# mouseproxy.net
KiCad netlist of a schematic drawn in EAGLE
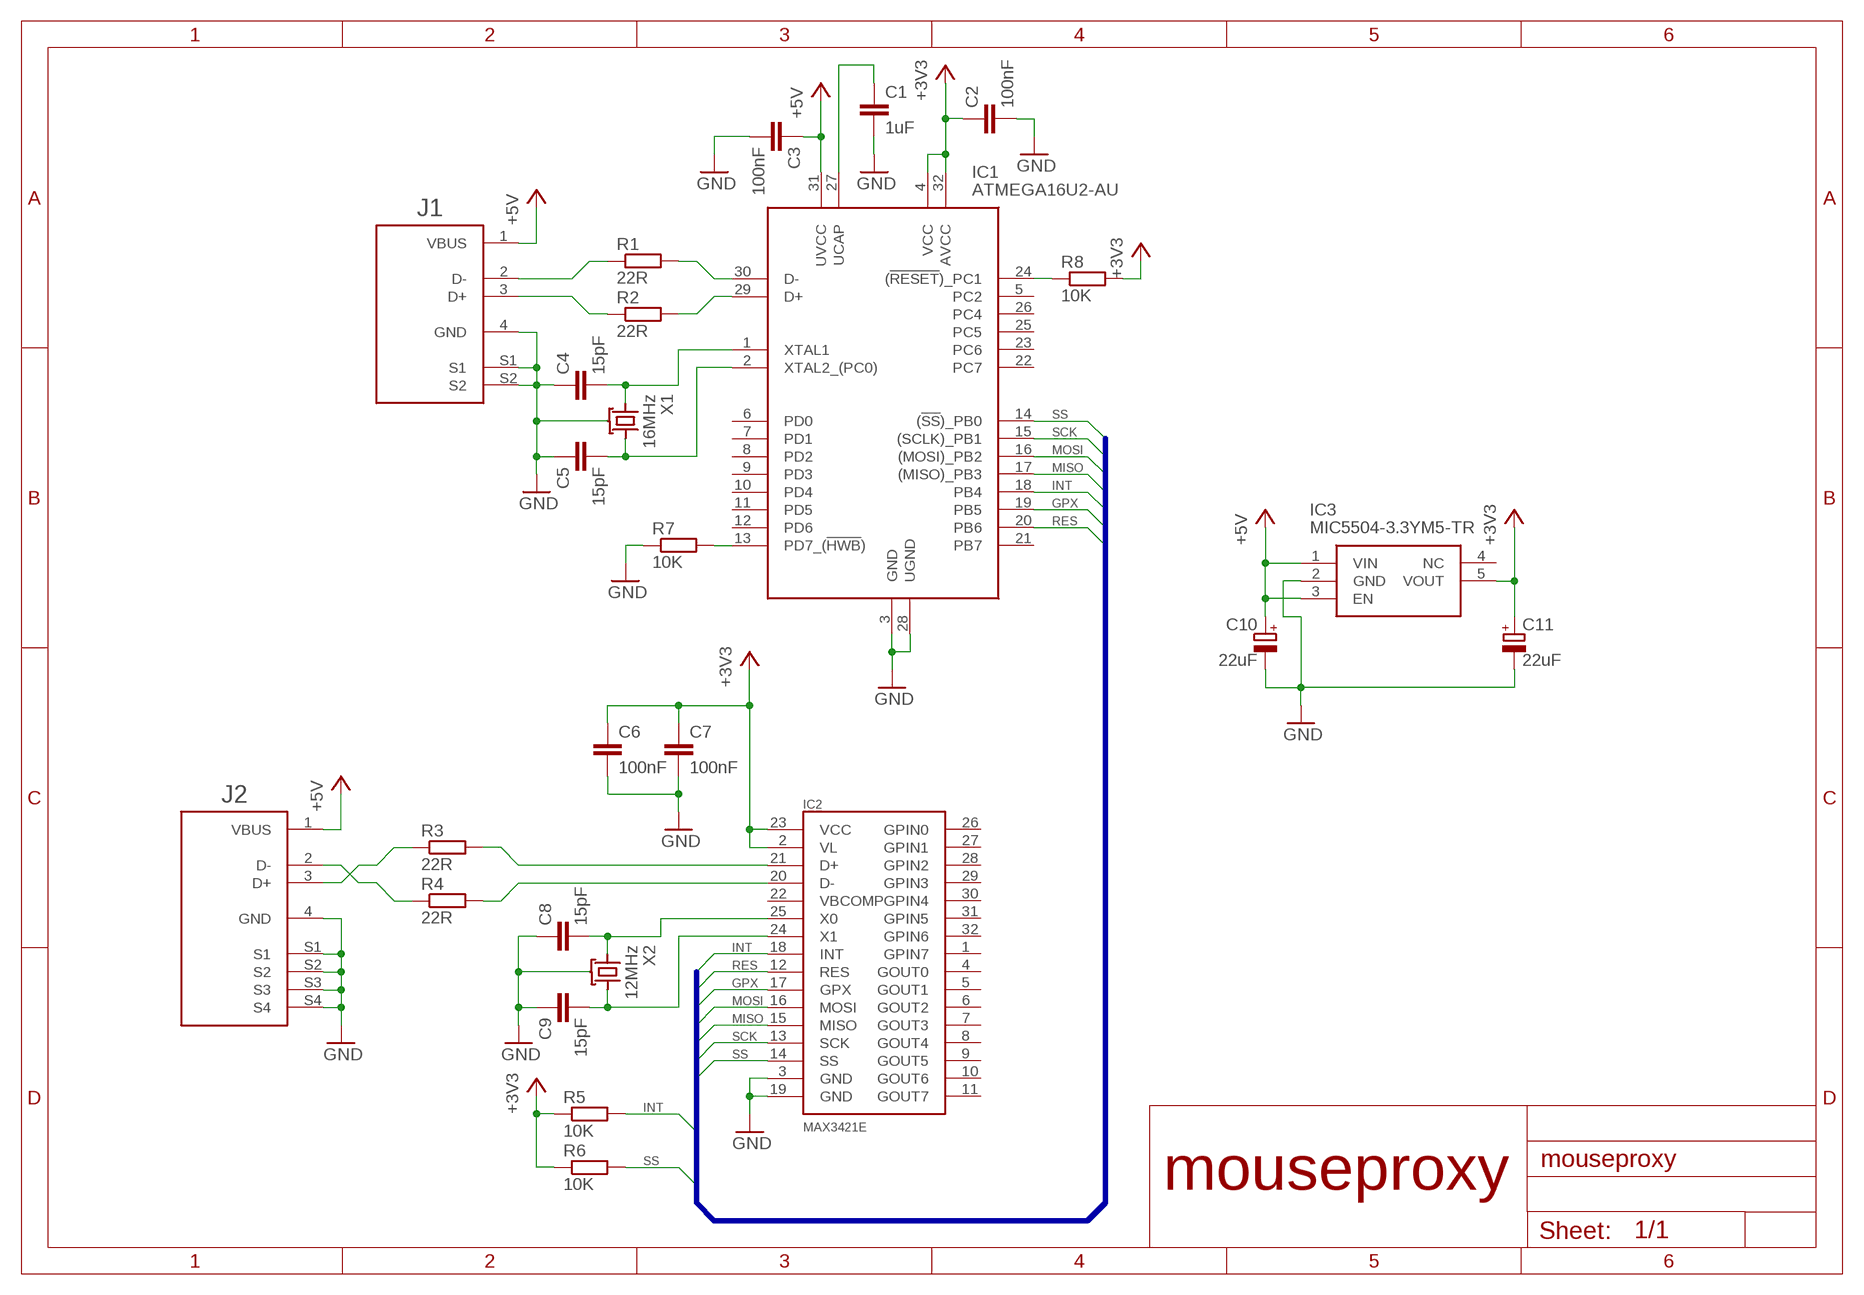
[diagram p0: schematic, sheet 1]

(export (version "E")
  (design (tool "Eeschema 10.0.6"))
  (components
    (comp (ref "C1")
      (value "1uF")
      (footprint "eagle-import:0603")
      (libsource (lib "eagle-import") (part "C0603"))
    )
    (comp (ref "C2")
      (value "100nF")
      (footprint "eagle-import:0603")
      (libsource (lib "eagle-import") (part "C0603"))
    )
    (comp (ref "C3")
      (value "100nF")
      (footprint "eagle-import:0603")
      (libsource (lib "eagle-import") (part "C0603"))
    )
    (comp (ref "C4")
      (value "15pF")
      (footprint "eagle-import:0603")
      (libsource (lib "eagle-import") (part "C0603"))
    )
    (comp (ref "C5")
      (value "15pF")
      (footprint "eagle-import:0603")
      (libsource (lib "eagle-import") (part "C0603"))
    )
    (comp (ref "C6")
      (value "100nF")
      (footprint "eagle-import:0603")
      (libsource (lib "eagle-import") (part "C0603"))
    )
    (comp (ref "C7")
      (value "100nF")
      (footprint "eagle-import:0603")
      (libsource (lib "eagle-import") (part "C0603"))
    )
    (comp (ref "C8")
      (value "15pF")
      (footprint "eagle-import:0603")
      (libsource (lib "eagle-import") (part "C0603"))
    )
    (comp (ref "C9")
      (value "15pF")
      (footprint "eagle-import:0603")
      (libsource (lib "eagle-import") (part "C0603"))
    )
    (comp (ref "C10")
      (value "22uF")
      (footprint "eagle-import:1206POL")
      (libsource (lib "eagle-import") (part "CPOL1206"))
    )
    (comp (ref "C11")
      (value "22uF")
      (footprint "eagle-import:1206POL")
      (libsource (lib "eagle-import") (part "CPOL1206"))
    )
    (comp (ref "IC1")
      (value "ATMEGA16U2-AU")
      (footprint "eagle-import:QFP80P900X900X120-32N")
      (fields
        (field (name "MOUSER_PART_NUMBER") "556-ATMEGA16U2-AU")
        (field (name "RS_PART_NUMBER") "1278282P")
      )
      (libsource (lib "eagle-import") (part "ATMEGA16U2-AU"))
    )
    (comp (ref "IC2")
      (value "MAX3421E")
      (footprint "eagle-import:TQFP32-5MM")
      (fields (field (name "MF") "Maxim Integrated"))
      (libsource (lib "eagle-import") (part "MAX3421E"))
    )
    (comp (ref "IC3")
      (value "MIC5504-3.3YM5-TR")
      (footprint "eagle-import:SOT95P280X130-5N")
      (fields
        (field (name "MOUSER_PART_NUMBER") "998-MIC5504-3.3YM5TR")
        (field (name "RS_PART_NUMBER") "9113332P")
      )
      (libsource (lib "eagle-import") (part "MIC5504-3.3YM5-TR"))
    )
    (comp (ref "J1")
      (value "48037-0001")
      (footprint "eagle-import:48037-0001")
      (libsource (lib "eagle-import") (part "48037-0001"))
    )
    (comp (ref "J2")
      (value "48258-0001")
      (footprint "eagle-import:48258-0001")
      (libsource (lib "eagle-import") (part "48258-0001"))
    )
    (comp (ref "R1")
      (value "22R")
      (footprint "eagle-import:0603")
      (libsource (lib "eagle-import") (part "R0603"))
    )
    (comp (ref "R2")
      (value "22R")
      (footprint "eagle-import:0603")
      (libsource (lib "eagle-import") (part "R0603"))
    )
    (comp (ref "R3")
      (value "22R")
      (footprint "eagle-import:0603")
      (libsource (lib "eagle-import") (part "R0603"))
    )
    (comp (ref "R4")
      (value "22R")
      (footprint "eagle-import:0603")
      (libsource (lib "eagle-import") (part "R0603"))
    )
    (comp (ref "R5")
      (value "10K")
      (footprint "eagle-import:0603")
      (libsource (lib "eagle-import") (part "R0603"))
    )
    (comp (ref "R6")
      (value "10K")
      (footprint "eagle-import:0603")
      (libsource (lib "eagle-import") (part "R0603"))
    )
    (comp (ref "R7")
      (value "10K")
      (footprint "eagle-import:0603")
      (libsource (lib "eagle-import") (part "R0603"))
    )
    (comp (ref "R8")
      (value "10K")
      (footprint "eagle-import:0603")
      (libsource (lib "eagle-import") (part "R0603"))
    )
    (comp (ref "X1")
      (value "16MHz")
      (footprint "eagle-import:3.2X2.5_4")
      (libsource (lib "eagle-import") (part "CRYSTAL_SHIELDED3.2X2.5"))
    )
    (comp (ref "X2")
      (value "12MHz")
      (footprint "eagle-import:3.2X2.5_4")
      (libsource (lib "eagle-import") (part "CRYSTAL_SHIELDED3.2X2.5"))
    )
  )
  (nets
    (net (code "1") (name "+3V3") (class "Default")
      (node (ref "C11") (pin "1") (pinfunction "+_1") (pintype "passive"))
      (node (ref "C2") (pin "1") (pinfunction "1_1") (pintype "passive"))
      (node (ref "C6") (pin "1") (pinfunction "1_1") (pintype "passive"))
      (node (ref "C7") (pin "1") (pinfunction "1_1") (pintype "passive"))
      (node (ref "IC1") (pin "32") (pinfunction "AVCC_32") (pintype "bidirectional"))
      (node (ref "IC1") (pin "4") (pinfunction "VCC_4") (pintype "bidirectional"))
      (node (ref "IC2") (pin "2") (pinfunction "VL_2") (pintype "bidirectional"))
      (node (ref "IC2") (pin "23") (pinfunction "VCC_23") (pintype "bidirectional"))
      (node (ref "IC3") (pin "5") (pinfunction "VOUT_5") (pintype "output"))
      (node (ref "R5") (pin "1") (pinfunction "1_1") (pintype "passive"))
      (node (ref "R6") (pin "1") (pinfunction "1_1") (pintype "passive"))
      (node (ref "R8") (pin "2") (pinfunction "2_2") (pintype "passive"))
    )
    (net (code "2") (name "+5V") (class "Default")
      (node (ref "C10") (pin "1") (pinfunction "+_1") (pintype "passive"))
      (node (ref "C3") (pin "1") (pinfunction "1_1") (pintype "passive"))
      (node (ref "IC1") (pin "31") (pinfunction "UVCC_31") (pintype "bidirectional"))
      (node (ref "IC3") (pin "1") (pinfunction "VIN_1") (pintype "input"))
      (node (ref "IC3") (pin "3") (pinfunction "EN_3") (pintype "bidirectional"))
      (node (ref "J1") (pin "1") (pinfunction "VBUS_1") (pintype "bidirectional"))
      (node (ref "J2") (pin "1") (pinfunction "VBUS_1") (pintype "bidirectional"))
    )
    (net (code "3") (name "/GPX") (class "Default")
      (node (ref "IC1") (pin "19") (pinfunction "PB5_19") (pintype "bidirectional"))
      (node (ref "IC2") (pin "17") (pinfunction "GPX_17") (pintype "bidirectional"))
    )
    (net (code "4") (name "/INT") (class "Default")
      (node (ref "IC1") (pin "18") (pinfunction "PB4_18") (pintype "bidirectional"))
      (node (ref "IC2") (pin "18") (pinfunction "INT_18") (pintype "bidirectional"))
      (node (ref "R5") (pin "2") (pinfunction "2_2") (pintype "passive"))
    )
    (net (code "5") (name "/MISO") (class "Default")
      (node (ref "IC1") (pin "17") (pinfunction "(MISO)_PB3_17") (pintype "bidirectional"))
      (node (ref "IC2") (pin "15") (pinfunction "MISO_15") (pintype "bidirectional"))
    )
    (net (code "6") (name "/MOSI") (class "Default")
      (node (ref "IC1") (pin "16") (pinfunction "(MOSI)_PB2_16") (pintype "bidirectional"))
      (node (ref "IC2") (pin "16") (pinfunction "MOSI_16") (pintype "bidirectional"))
    )
    (net (code "7") (name "/RES") (class "Default")
      (node (ref "IC1") (pin "20") (pinfunction "PB6_20") (pintype "bidirectional"))
      (node (ref "IC2") (pin "12") (pinfunction "RES_12") (pintype "bidirectional"))
    )
    (net (code "8") (name "/SCK") (class "Default")
      (node (ref "IC1") (pin "15") (pinfunction "(SCLK)_PB1_15") (pintype "bidirectional"))
      (node (ref "IC2") (pin "13") (pinfunction "SCK_13") (pintype "bidirectional"))
    )
    (net (code "9") (name "/SS") (class "Default")
      (node (ref "IC1") (pin "14") (pinfunction "(~{SS})_PB0_14") (pintype "bidirectional"))
      (node (ref "IC2") (pin "14") (pinfunction "SS_14") (pintype "bidirectional"))
      (node (ref "R6") (pin "2") (pinfunction "2_2") (pintype "passive"))
    )
    (net (code "10") (name "GND") (class "Default")
      (node (ref "C1") (pin "2") (pinfunction "2_2") (pintype "passive"))
      (node (ref "C10") (pin "2") (pinfunction "-_2") (pintype "passive"))
      (node (ref "C11") (pin "2") (pinfunction "-_2") (pintype "passive"))
      (node (ref "C2") (pin "2") (pinfunction "2_2") (pintype "passive"))
      (node (ref "C3") (pin "2") (pinfunction "2_2") (pintype "passive"))
      (node (ref "C4") (pin "1") (pinfunction "1_1") (pintype "passive"))
      (node (ref "C5") (pin "1") (pinfunction "1_1") (pintype "passive"))
      (node (ref "C6") (pin "2") (pinfunction "2_2") (pintype "passive"))
      (node (ref "C7") (pin "2") (pinfunction "2_2") (pintype "passive"))
      (node (ref "C8") (pin "1") (pinfunction "1_1") (pintype "passive"))
      (node (ref "C9") (pin "1") (pinfunction "1_1") (pintype "passive"))
      (node (ref "IC1") (pin "28") (pinfunction "UGND_28") (pintype "bidirectional"))
      (node (ref "IC1") (pin "3") (pinfunction "GND_3") (pintype "bidirectional"))
      (node (ref "IC2") (pin "19") (pinfunction "GND_19") (pintype "bidirectional"))
      (node (ref "IC2") (pin "3") (pinfunction "GND_3") (pintype "bidirectional"))
      (node (ref "IC3") (pin "2") (pinfunction "GND_2") (pintype "power_in"))
      (node (ref "J1") (pin "4") (pinfunction "GND_4") (pintype "bidirectional"))
      (node (ref "J1") (pin "S1") (pinfunction "S1_S1") (pintype "bidirectional"))
      (node (ref "J1") (pin "S2") (pinfunction "S2_S2") (pintype "bidirectional"))
      (node (ref "J2") (pin "4") (pinfunction "GND_4") (pintype "bidirectional"))
      (node (ref "J2") (pin "S1") (pinfunction "S1_S1") (pintype "bidirectional"))
      (node (ref "J2") (pin "S2") (pinfunction "S2_S2") (pintype "bidirectional"))
      (node (ref "J2") (pin "S3") (pinfunction "S3_S3") (pintype "bidirectional"))
      (node (ref "J2") (pin "S4") (pinfunction "S4_S4") (pintype "bidirectional"))
      (node (ref "R7") (pin "1") (pinfunction "1_1") (pintype "passive"))
      (node (ref "X1") (pin "P$2") (pinfunction "GND_P$2") (pintype "power_in"))
      (node (ref "X1") (pin "P$4") (pinfunction "GND_P$4") (pintype "power_in"))
      (node (ref "X2") (pin "P$2") (pinfunction "GND_P$2") (pintype "power_in"))
      (node (ref "X2") (pin "P$4") (pinfunction "GND_P$4") (pintype "power_in"))
    )
    (net (code "11") (name "Net-(IC1-(~{RESET})_PC1)") (class "Default")
      (node (ref "IC1") (pin "24") (pinfunction "(~{RESET})_PC1_24") (pintype "bidirectional"))
      (node (ref "R8") (pin "1") (pinfunction "1_1") (pintype "passive"))
    )
    (net (code "12") (name "Net-(IC1-D+)") (class "Default")
      (node (ref "IC1") (pin "29") (pinfunction "D+_29") (pintype "bidirectional"))
      (node (ref "R2") (pin "2") (pinfunction "2_2") (pintype "passive"))
    )
    (net (code "13") (name "Net-(IC1-D-)") (class "Default")
      (node (ref "IC1") (pin "30") (pinfunction "D-_30") (pintype "bidirectional"))
      (node (ref "R1") (pin "2") (pinfunction "2_2") (pintype "passive"))
    )
    (net (code "14") (name "Net-(IC1-PD7_(~{HWB}))") (class "Default")
      (node (ref "IC1") (pin "13") (pinfunction "PD7_(~{HWB})_13") (pintype "bidirectional"))
      (node (ref "R7") (pin "2") (pinfunction "2_2") (pintype "passive"))
    )
    (net (code "15") (name "Net-(IC1-UCAP)") (class "Default")
      (node (ref "C1") (pin "1") (pinfunction "1_1") (pintype "passive"))
      (node (ref "IC1") (pin "27") (pinfunction "UCAP_27") (pintype "bidirectional"))
    )
    (net (code "16") (name "Net-(IC1-XTAL1)") (class "Default")
      (node (ref "C4") (pin "2") (pinfunction "2_2") (pintype "passive"))
      (node (ref "IC1") (pin "1") (pinfunction "XTAL1_1") (pintype "bidirectional"))
      (node (ref "X1") (pin "P$1") (pinfunction "XT1_P$1") (pintype "bidirectional"))
    )
    (net (code "17") (name "Net-(IC1-XTAL2_(PC0))") (class "Default")
      (node (ref "C5") (pin "2") (pinfunction "2_2") (pintype "passive"))
      (node (ref "IC1") (pin "2") (pinfunction "XTAL2_(PC0)_2") (pintype "bidirectional"))
      (node (ref "X1") (pin "P$3") (pinfunction "XT2_P$3") (pintype "bidirectional"))
    )
    (net (code "18") (name "Net-(IC2-D+)") (class "Default")
      (node (ref "IC2") (pin "21") (pinfunction "D+_21") (pintype "bidirectional"))
      (node (ref "R3") (pin "2") (pinfunction "2_2") (pintype "passive"))
    )
    (net (code "19") (name "Net-(IC2-D-)") (class "Default")
      (node (ref "IC2") (pin "20") (pinfunction "D-_20") (pintype "bidirectional"))
      (node (ref "R4") (pin "2") (pinfunction "2_2") (pintype "passive"))
    )
    (net (code "20") (name "Net-(IC2-X0)") (class "Default")
      (node (ref "C8") (pin "2") (pinfunction "2_2") (pintype "passive"))
      (node (ref "IC2") (pin "25") (pinfunction "X0_25") (pintype "bidirectional"))
      (node (ref "X2") (pin "P$1") (pinfunction "XT1_P$1") (pintype "bidirectional"))
    )
    (net (code "21") (name "Net-(IC2-X1)") (class "Default")
      (node (ref "C9") (pin "2") (pinfunction "2_2") (pintype "passive"))
      (node (ref "IC2") (pin "24") (pinfunction "X1_24") (pintype "bidirectional"))
      (node (ref "X2") (pin "P$3") (pinfunction "XT2_P$3") (pintype "bidirectional"))
    )
    (net (code "22") (name "Net-(J1-D+)") (class "Default")
      (node (ref "J1") (pin "3") (pinfunction "D+_3") (pintype "bidirectional"))
      (node (ref "R2") (pin "1") (pinfunction "1_1") (pintype "passive"))
    )
    (net (code "23") (name "Net-(J1-D-)") (class "Default")
      (node (ref "J1") (pin "2") (pinfunction "D-_2") (pintype "bidirectional"))
      (node (ref "R1") (pin "1") (pinfunction "1_1") (pintype "passive"))
    )
    (net (code "24") (name "Net-(J2-D+)") (class "Default")
      (node (ref "J2") (pin "3") (pinfunction "D+_3") (pintype "bidirectional"))
      (node (ref "R3") (pin "1") (pinfunction "1_1") (pintype "passive"))
    )
    (net (code "25") (name "Net-(J2-D-)") (class "Default")
      (node (ref "J2") (pin "2") (pinfunction "D-_2") (pintype "bidirectional"))
      (node (ref "R4") (pin "1") (pinfunction "1_1") (pintype "passive"))
    )
    (net (code "26") (name "unconnected-(IC1-PB7-Pad21)") (class "Default")
      (node (ref "IC1") (pin "21") (pinfunction "PB7_21") (pintype "bidirectional"))
    )
    (net (code "27") (name "unconnected-(IC1-PC2-Pad5)") (class "Default")
      (node (ref "IC1") (pin "5") (pinfunction "PC2_5") (pintype "bidirectional"))
    )
    (net (code "28") (name "unconnected-(IC1-PC4-Pad26)") (class "Default")
      (node (ref "IC1") (pin "26") (pinfunction "PC4_26") (pintype "bidirectional"))
    )
    (net (code "29") (name "unconnected-(IC1-PC5-Pad25)") (class "Default")
      (node (ref "IC1") (pin "25") (pinfunction "PC5_25") (pintype "bidirectional"))
    )
    (net (code "30") (name "unconnected-(IC1-PC6-Pad23)") (class "Default")
      (node (ref "IC1") (pin "23") (pinfunction "PC6_23") (pintype "bidirectional"))
    )
    (net (code "31") (name "unconnected-(IC1-PC7-Pad22)") (class "Default")
      (node (ref "IC1") (pin "22") (pinfunction "PC7_22") (pintype "bidirectional"))
    )
    (net (code "32") (name "unconnected-(IC1-PD0-Pad6)") (class "Default")
      (node (ref "IC1") (pin "6") (pinfunction "PD0_6") (pintype "bidirectional"))
    )
    (net (code "33") (name "unconnected-(IC1-PD1-Pad7)") (class "Default")
      (node (ref "IC1") (pin "7") (pinfunction "PD1_7") (pintype "bidirectional"))
    )
    (net (code "34") (name "unconnected-(IC1-PD2-Pad8)") (class "Default")
      (node (ref "IC1") (pin "8") (pinfunction "PD2_8") (pintype "bidirectional"))
    )
    (net (code "35") (name "unconnected-(IC1-PD3-Pad9)") (class "Default")
      (node (ref "IC1") (pin "9") (pinfunction "PD3_9") (pintype "bidirectional"))
    )
    (net (code "36") (name "unconnected-(IC1-PD4-Pad10)") (class "Default")
      (node (ref "IC1") (pin "10") (pinfunction "PD4_10") (pintype "bidirectional"))
    )
    (net (code "37") (name "unconnected-(IC1-PD5-Pad11)") (class "Default")
      (node (ref "IC1") (pin "11") (pinfunction "PD5_11") (pintype "bidirectional"))
    )
    (net (code "38") (name "unconnected-(IC1-PD6-Pad12)") (class "Default")
      (node (ref "IC1") (pin "12") (pinfunction "PD6_12") (pintype "bidirectional"))
    )
    (net (code "39") (name "unconnected-(IC2-GOUT0-Pad4)") (class "Default")
      (node (ref "IC2") (pin "4") (pinfunction "GOUT0_4") (pintype "bidirectional"))
    )
    (net (code "40") (name "unconnected-(IC2-GOUT1-Pad5)") (class "Default")
      (node (ref "IC2") (pin "5") (pinfunction "GOUT1_5") (pintype "bidirectional"))
    )
    (net (code "41") (name "unconnected-(IC2-GOUT2-Pad6)") (class "Default")
      (node (ref "IC2") (pin "6") (pinfunction "GOUT2_6") (pintype "bidirectional"))
    )
    (net (code "42") (name "unconnected-(IC2-GOUT3-Pad7)") (class "Default")
      (node (ref "IC2") (pin "7") (pinfunction "GOUT3_7") (pintype "bidirectional"))
    )
    (net (code "43") (name "unconnected-(IC2-GOUT4-Pad8)") (class "Default")
      (node (ref "IC2") (pin "8") (pinfunction "GOUT4_8") (pintype "bidirectional"))
    )
    (net (code "44") (name "unconnected-(IC2-GOUT5-Pad9)") (class "Default")
      (node (ref "IC2") (pin "9") (pinfunction "GOUT5_9") (pintype "bidirectional"))
    )
    (net (code "45") (name "unconnected-(IC2-GOUT6-Pad10)") (class "Default")
      (node (ref "IC2") (pin "10") (pinfunction "GOUT6_10") (pintype "bidirectional"))
    )
    (net (code "46") (name "unconnected-(IC2-GOUT7-Pad11)") (class "Default")
      (node (ref "IC2") (pin "11") (pinfunction "GOUT7_11") (pintype "bidirectional"))
    )
    (net (code "47") (name "unconnected-(IC2-GPIN0-Pad26)") (class "Default")
      (node (ref "IC2") (pin "26") (pinfunction "GPIN0_26") (pintype "bidirectional"))
    )
    (net (code "48") (name "unconnected-(IC2-GPIN1-Pad27)") (class "Default")
      (node (ref "IC2") (pin "27") (pinfunction "GPIN1_27") (pintype "bidirectional"))
    )
    (net (code "49") (name "unconnected-(IC2-GPIN2-Pad28)") (class "Default")
      (node (ref "IC2") (pin "28") (pinfunction "GPIN2_28") (pintype "bidirectional"))
    )
    (net (code "50") (name "unconnected-(IC2-GPIN3-Pad29)") (class "Default")
      (node (ref "IC2") (pin "29") (pinfunction "GPIN3_29") (pintype "bidirectional"))
    )
    (net (code "51") (name "unconnected-(IC2-GPIN4-Pad30)") (class "Default")
      (node (ref "IC2") (pin "30") (pinfunction "GPIN4_30") (pintype "bidirectional"))
    )
    (net (code "52") (name "unconnected-(IC2-GPIN5-Pad31)") (class "Default")
      (node (ref "IC2") (pin "31") (pinfunction "GPIN5_31") (pintype "bidirectional"))
    )
    (net (code "53") (name "unconnected-(IC2-GPIN6-Pad32)") (class "Default")
      (node (ref "IC2") (pin "32") (pinfunction "GPIN6_32") (pintype "bidirectional"))
    )
    (net (code "54") (name "unconnected-(IC2-GPIN7-Pad1)") (class "Default")
      (node (ref "IC2") (pin "1") (pinfunction "GPIN7_1") (pintype "bidirectional"))
    )
    (net (code "55") (name "unconnected-(IC2-VBCOMP-Pad22)") (class "Default")
      (node (ref "IC2") (pin "22") (pinfunction "VBCOMP_22") (pintype "bidirectional"))
    )
    (net (code "56") (name "unconnected-(IC3-NC-Pad4)") (class "Default")
      (node (ref "IC3") (pin "4") (pinfunction "NC_4") (pintype "no_connect"))
    )
  )
)
